# Li-IonSwProtect.net
KiCad netlist of a schematic drawn in EAGLE
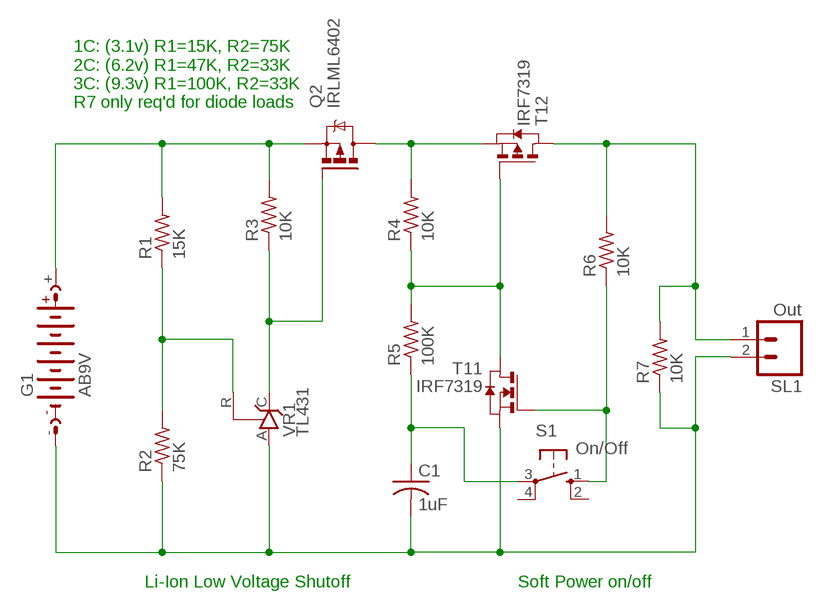
[diagram p0: schematic, sheet 1]

(export (version "E")
  (design (tool "Eeschema 10.0.6"))
  (components
    (comp (ref "C1")
      (value "1uF")
      (footprint "eagle-import:C0805")
      (libsource (lib "eagle-import") (part "C-USC0805"))
    )
    (comp (ref "G1")
      (value "AB9V")
      (footprint "eagle-import:AB9V")
      (libsource (lib "eagle-import") (part "AB9V"))
    )
    (comp (ref "Q2")
      (value "IRLML6402")
      (footprint "eagle-import:MICRO3")
      (libsource (lib "eagle-import") (part "IRLML5203"))
    )
    (comp (ref "R1")
      (value "15K")
      (footprint "eagle-import:R0805")
      (libsource (lib "eagle-import") (part "R-US_R0805"))
    )
    (comp (ref "R2")
      (value "75K")
      (footprint "eagle-import:R0805")
      (libsource (lib "eagle-import") (part "R-US_R0805"))
    )
    (comp (ref "R3")
      (value "10K")
      (footprint "eagle-import:R0805")
      (libsource (lib "eagle-import") (part "R-US_R0805"))
    )
    (comp (ref "R4")
      (value "10K")
      (footprint "eagle-import:R0805")
      (libsource (lib "eagle-import") (part "R-US_R0805"))
    )
    (comp (ref "R5")
      (value "100K")
      (footprint "eagle-import:R0805")
      (libsource (lib "eagle-import") (part "R-US_R0805"))
    )
    (comp (ref "R6")
      (value "10K")
      (footprint "eagle-import:R0805")
      (libsource (lib "eagle-import") (part "R-US_R0805"))
    )
    (comp (ref "R7")
      (value "10K")
      (footprint "eagle-import:R0805")
      (libsource (lib "eagle-import") (part "R-US_R0805"))
    )
    (comp (ref "S1")
      (value "On/Off")
      (footprint "eagle-import:B3F-10XX")
      (fields (field (name "MPN") "B3F-1000"))
      (libsource (lib "eagle-import") (part "10-XX"))
    )
    (comp (ref "SL1")
      (value "Out")
      (footprint "eagle-import:02P")
      (libsource (lib "eagle-import") (part "M02"))
    )
    (comp (ref "T1")
      (value "IRF7319")
      (footprint "eagle-import:SO8")
      (libsource (lib "eagle-import") (part "PN_MOSFET-SO8"))
    )
    (comp (ref "VR1")
      (value "TL431")
      (footprint "eagle-import:TO92-CLP")
      (libsource (lib "eagle-import") (part "TL431CLP"))
    )
  )
  (nets
    (net (code "1") (name "Net-(Q2-D)") (class "Default")
      (node (ref "Q2") (pin "3") (pinfunction "D_3") (pintype "passive"))
      (node (ref "R4") (pin "2") (pinfunction "2_2") (pintype "passive"))
      (node (ref "T1") (pin "3") (pinfunction "S_3") (pintype "passive"))
    )
    (net (code "2") (name "Net-(Q2-G)") (class "Default")
      (node (ref "Q2") (pin "1") (pinfunction "G_1") (pintype "passive"))
      (node (ref "R3") (pin "1") (pinfunction "1_1") (pintype "passive"))
      (node (ref "VR1") (pin "C") (pinfunction "C_C") (pintype "passive"))
    )
    (net (code "3") (name "Net-(Q2-S)") (class "Default")
      (node (ref "G1") (pin "+") (pinfunction "+_+") (pintype "passive"))
      (node (ref "Q2") (pin "2") (pinfunction "S_2") (pintype "passive"))
      (node (ref "R1") (pin "2") (pinfunction "2_2") (pintype "passive"))
      (node (ref "R3") (pin "2") (pinfunction "2_2") (pintype "passive"))
    )
    (net (code "4") (name "Net-(R1-Pad1)") (class "Default")
      (node (ref "R1") (pin "1") (pinfunction "1_1") (pintype "passive"))
      (node (ref "R2") (pin "2") (pinfunction "2_2") (pintype "passive"))
      (node (ref "VR1") (pin "R") (pinfunction "R_R") (pintype "passive"))
    )
    (net (code "5") (name "Net-(R6-Pad2)") (class "Default")
      (node (ref "R6") (pin "2") (pinfunction "2_2") (pintype "passive"))
      (node (ref "R7") (pin "2") (pinfunction "2_2") (pintype "passive"))
      (node (ref "SL1") (pin "1") (pinfunction "1_1") (pintype "passive"))
      (node (ref "T1") (pin "5") (pinfunction "D_5") (pintype "passive"))
      (node (ref "T1") (pin "6") (pinfunction "D_6") (pintype "passive"))
    )
    (net (code "6") (name "Net-(S1-P)") (class "Default")
      (node (ref "C1") (pin "1") (pinfunction "1_1") (pintype "passive"))
      (node (ref "R5") (pin "1") (pinfunction "1_1") (pintype "passive"))
      (node (ref "S1") (pin "3") (pinfunction "P_3") (pintype "passive"))
    )
    (net (code "7") (name "Net-(S1-S)") (class "Default")
      (node (ref "R6") (pin "1") (pinfunction "1_1") (pintype "passive"))
      (node (ref "S1") (pin "1") (pinfunction "S_1") (pintype "passive"))
      (node (ref "T1") (pin "2") (pinfunction "G_2") (pintype "passive"))
    )
    (net (code "8") (name "Net-(T1A-S)") (class "Default")
      (node (ref "C1") (pin "2") (pinfunction "2_2") (pintype "passive"))
      (node (ref "G1") (pin "-") (pinfunction "-_-") (pintype "passive"))
      (node (ref "R2") (pin "1") (pinfunction "1_1") (pintype "passive"))
      (node (ref "R7") (pin "1") (pinfunction "1_1") (pintype "passive"))
      (node (ref "SL1") (pin "2") (pinfunction "2_2") (pintype "passive"))
      (node (ref "T1") (pin "1") (pinfunction "S_1") (pintype "passive"))
      (node (ref "VR1") (pin "A") (pinfunction "A_A") (pintype "passive"))
    )
    (net (code "9") (name "Net-(T1B-G)") (class "Default")
      (node (ref "R4") (pin "1") (pinfunction "1_1") (pintype "passive"))
      (node (ref "R5") (pin "2") (pinfunction "2_2") (pintype "passive"))
      (node (ref "T1") (pin "4") (pinfunction "G_4") (pintype "passive"))
      (node (ref "T1") (pin "7") (pinfunction "D_7") (pintype "passive"))
      (node (ref "T1") (pin "8") (pinfunction "D_8") (pintype "passive"))
    )
    (net (code "10") (name "unconnected-(S1-P1-Pad4)") (class "Default")
      (node (ref "S1") (pin "4") (pinfunction "P1_4") (pintype "passive"))
    )
    (net (code "11") (name "unconnected-(S1-S1-Pad2)") (class "Default")
      (node (ref "S1") (pin "2") (pinfunction "S1_2") (pintype "passive"))
    )
  )
)
